# Whale_Lamp-jlc-v2.net
KiCad netlist of a schematic drawn in EAGLE
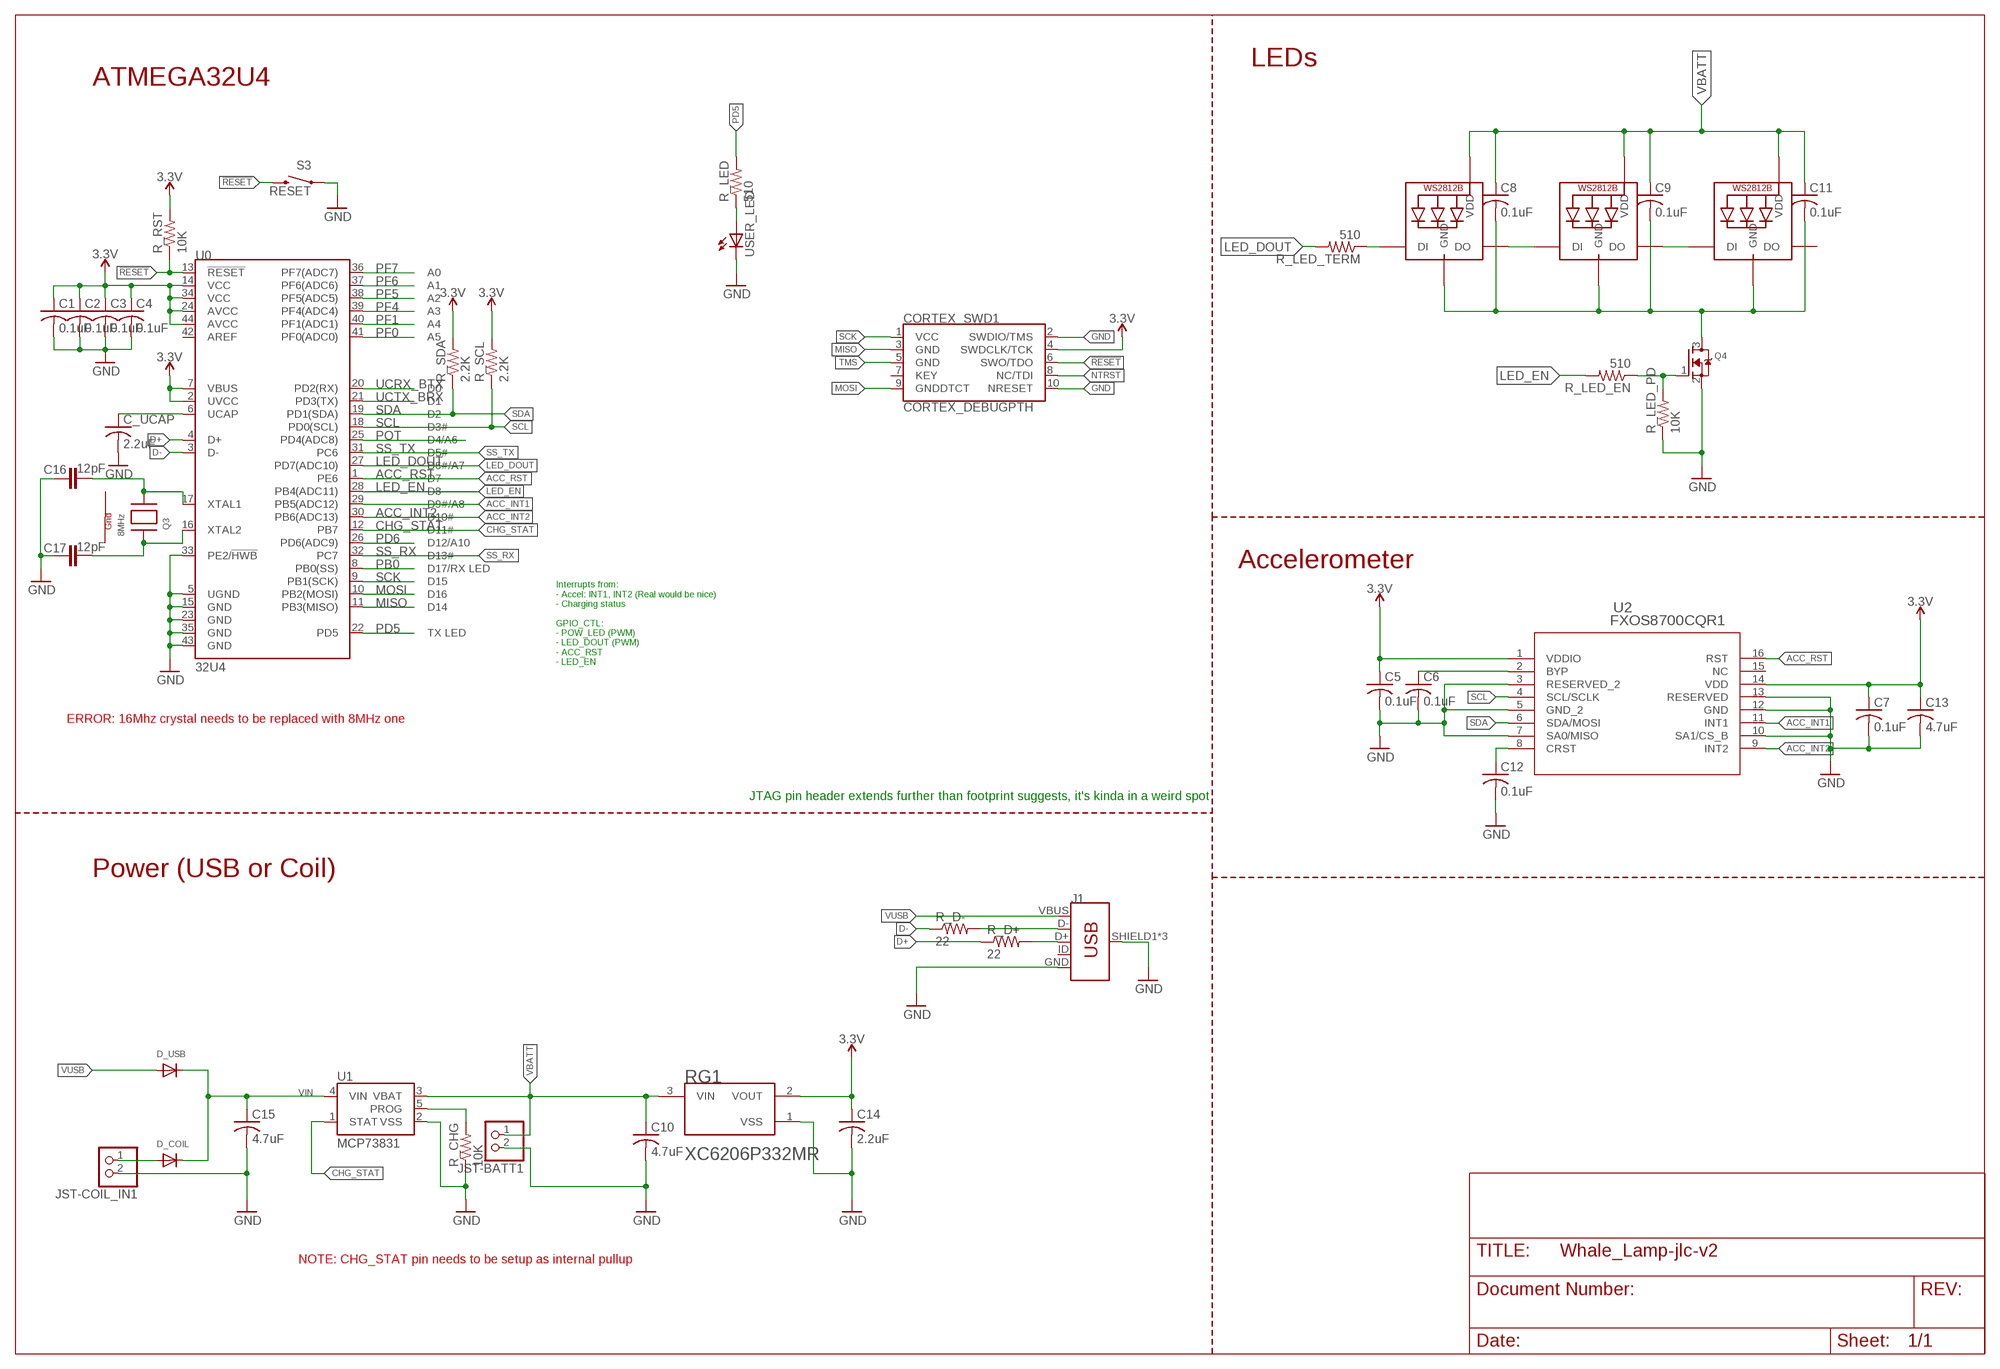
[diagram p0: schematic, sheet 1]

(export (version "E")
  (design (tool "Eeschema 10.0.6"))
  (components
    (comp (ref "C1")
      (value "0.1uF")
      (footprint "eagle-import:C0402")
      (libsource (lib "eagle-import") (part "C-USC0402"))
    )
    (comp (ref "C2")
      (value "0.1uF")
      (footprint "eagle-import:C0402")
      (libsource (lib "eagle-import") (part "C-USC0402"))
    )
    (comp (ref "C3")
      (value "0.1uF")
      (footprint "eagle-import:C0402")
      (libsource (lib "eagle-import") (part "C-USC0402"))
    )
    (comp (ref "C4")
      (value "0.1uF")
      (footprint "eagle-import:C0402")
      (libsource (lib "eagle-import") (part "C-USC0402"))
    )
    (comp (ref "C5")
      (value "0.1uF")
      (footprint "eagle-import:C0402")
      (libsource (lib "eagle-import") (part "C-USC0402"))
    )
    (comp (ref "C6")
      (value "0.1uF")
      (footprint "eagle-import:C0402")
      (libsource (lib "eagle-import") (part "C-USC0402"))
    )
    (comp (ref "C7")
      (value "0.1uF")
      (footprint "eagle-import:C0402")
      (libsource (lib "eagle-import") (part "C-USC0402"))
    )
    (comp (ref "C8")
      (value "0.1uF")
      (footprint "eagle-import:C0402")
      (libsource (lib "eagle-import") (part "C-USC0402"))
    )
    (comp (ref "C9")
      (value "0.1uF")
      (footprint "eagle-import:C0402")
      (libsource (lib "eagle-import") (part "C-USC0402"))
    )
    (comp (ref "C10")
      (value "4.7uF")
      (footprint "eagle-import:C0603")
      (libsource (lib "eagle-import") (part "C-USC0603"))
    )
    (comp (ref "C11")
      (value "0.1uF")
      (footprint "eagle-import:C0402")
      (libsource (lib "eagle-import") (part "C-USC0402"))
    )
    (comp (ref "C12")
      (value "0.1uF")
      (footprint "eagle-import:C0402")
      (libsource (lib "eagle-import") (part "C-USC0402"))
    )
    (comp (ref "C13")
      (value "4.7uF")
      (footprint "eagle-import:C0603")
      (libsource (lib "eagle-import") (part "C-USC0603"))
    )
    (comp (ref "C14")
      (value "2.2uF")
      (footprint "eagle-import:C0603")
      (libsource (lib "eagle-import") (part "C-USC0603"))
    )
    (comp (ref "C15")
      (value "4.7uF")
      (footprint "eagle-import:C0603")
      (libsource (lib "eagle-import") (part "C-USC0603"))
    )
    (comp (ref "C16")
      (value "12pF")
      (footprint "eagle-import:0402-CAP")
      (libsource (lib "eagle-import") (part "CAP0402-CAP"))
    )
    (comp (ref "C17")
      (value "12pF")
      (footprint "eagle-import:0402-CAP")
      (libsource (lib "eagle-import") (part "CAP0402-CAP"))
    )
    (comp (ref "CORTEX_SWD1")
      (value "CORTEX_DEBUGPTH")
      (footprint "eagle-import:2X5-PTH-1.27MM")
      (libsource (lib "eagle-import") (part "CORTEX_DEBUGPTH"))
    )
    (comp (ref "C_UCAP")
      (value "2.2uF")
      (footprint "eagle-import:C0603")
      (libsource (lib "eagle-import") (part "C-USC0603"))
    )
    (comp (ref "D_COIL")
      (value "DIODESOD-123")
      (footprint "eagle-import:SOD-123")
      (libsource (lib "eagle-import") (part "DIODESOD-123"))
    )
    (comp (ref "D_USB")
      (value "DIODESOD-123")
      (footprint "eagle-import:SOD-123")
      (libsource (lib "eagle-import") (part "DIODESOD-123"))
    )
    (comp (ref "J1")
      (value "USB_MICRO-B_FEMALE-SMT")
      (footprint "eagle-import:USB-B-MICRO-SMD")
      (libsource (lib "eagle-import") (part "USB_MICRO-B_FEMALE-SMT"))
    )
    (comp (ref "JST-BATT1")
      (value "JST_2PIN-THM-RA")
      (footprint "eagle-import:JST-PH-2-THM-RA")
      (libsource (lib "eagle-import") (part "JST_2PIN-THM-RA"))
    )
    (comp (ref "JST-COIL_IN1")
      (value "JST_2PIN-THM-RA")
      (footprint "eagle-import:JST-PH-2-THM-RA")
      (libsource (lib "eagle-import") (part "JST_2PIN-THM-RA"))
    )
    (comp (ref "LED1")
      (value "WS2812B3535")
      (footprint "eagle-import:LED3535")
      (libsource (lib "eagle-import") (part "WS2812B3535"))
    )
    (comp (ref "LED2")
      (value "WS2812B3535")
      (footprint "eagle-import:LED3535")
      (libsource (lib "eagle-import") (part "WS2812B3535"))
    )
    (comp (ref "LED3")
      (value "WS2812B3535")
      (footprint "eagle-import:LED3535")
      (libsource (lib "eagle-import") (part "WS2812B3535"))
    )
    (comp (ref "Q3")
      (value "8MHz")
      (footprint "eagle-import:NX3225")
      (libsource (lib "eagle-import") (part "XTAL-4-3225"))
    )
    (comp (ref "Q4")
      (value "MOSFET-NREFLOW")
      (footprint "eagle-import:SOT23")
      (libsource (lib "eagle-import") (part "MOSFET-NREFLOW"))
    )
    (comp (ref "RG1")
      (value "TOREX_XC6206P332MRTOREX_XC6206P332MR_0_0")
      (footprint "eagle-import:TOREX_XC6206P332MR_0")
      (fields
        (field (name "MF") "Torex")
        (field (name "MOUSER_PART_NUMBER") "865-XC6206P332MR-G")
        (field (name "MPN") "XC6206P332MR")
      )
      (libsource (lib "eagle-import") (part "TOREX_XC6206P332MRTOREX_XC6206P332MR_0_0"))
    )
    (comp (ref "R_CHG")
      (value "10K")
      (footprint "eagle-import:R0402")
      (libsource (lib "eagle-import") (part "R-US_R0402"))
    )
    (comp (ref "R_D+")
      (value "22")
      (footprint "eagle-import:R0402")
      (libsource (lib "eagle-import") (part "R-US_R0402"))
    )
    (comp (ref "R_D-")
      (value "22")
      (footprint "eagle-import:R0402")
      (libsource (lib "eagle-import") (part "R-US_R0402"))
    )
    (comp (ref "R_LED")
      (value "510")
      (footprint "eagle-import:R0402")
      (libsource (lib "eagle-import") (part "R-US_R0402"))
    )
    (comp (ref "R_LED_EN")
      (value "510")
      (footprint "eagle-import:R0402")
      (libsource (lib "eagle-import") (part "R-US_R0402"))
    )
    (comp (ref "R_LED_PD")
      (value "10K")
      (footprint "eagle-import:R0402")
      (libsource (lib "eagle-import") (part "R-US_R0402"))
    )
    (comp (ref "R_LED_TERM")
      (value "510")
      (footprint "eagle-import:R0402")
      (libsource (lib "eagle-import") (part "R-US_R0402"))
    )
    (comp (ref "R_RST")
      (value "10K")
      (footprint "eagle-import:R0402")
      (libsource (lib "eagle-import") (part "R-US_R0402"))
    )
    (comp (ref "R_SCL")
      (value "2.2K")
      (footprint "eagle-import:R0402")
      (libsource (lib "eagle-import") (part "R-US_R0402"))
    )
    (comp (ref "R_SDA")
      (value "2.2K")
      (footprint "eagle-import:R0402")
      (libsource (lib "eagle-import") (part "R-US_R0402"))
    )
    (comp (ref "S3")
      (value "RESET")
      (footprint "eagle-import:TACTILE_SWITCH_SMD_4.6X2.8MM")
      (libsource (lib "eagle-import") (part "SWITCH-MOMENTARY-2SMD-4.6X2.8MM"))
    )
    (comp (ref "U0")
      (value "32U4")
      (footprint "eagle-import:QFN-44")
      (libsource (lib "eagle-import") (part "ATMEGA32U4QFN"))
    )
    (comp (ref "U1")
      (value "MCP73831")
      (footprint "eagle-import:SOT23-5")
      (libsource (lib "eagle-import") (part "MCP73831"))
    )
    (comp (ref "U2")
      (value "FXOS8700CQR1")
      (footprint "eagle-import:QFN16_3X3_NXP")
      (fields (field (name "COPYRIGHT") "Copyright (C) 2018 Accelerated Designs. All rights reserved"))
      (libsource (lib "eagle-import") (part "FXOS8700CQR1"))
    )
    (comp (ref "USER_LED")
      (value "LEDCHIPLED_0603")
      (footprint "eagle-import:CHIPLED_0603")
      (libsource (lib "eagle-import") (part "LEDCHIPLED_0603"))
    )
  )
  (nets
    (net (code "1") (name "/G1") (class "Default")
      (node (ref "Q3") (pin "4") (pinfunction "G1_4") (pintype "power_in"))
    )
    (net (code "2") (name "/G2") (class "Default")
      (node (ref "Q3") (pin "2") (pinfunction "G2_2") (pintype "power_in"))
    )
    (net (code "3") (name "/PB0") (class "Default")
      (node (ref "U0") (pin "8") (pinfunction "PB0(SS)_8") (pintype "bidirectional"))
    )
    (net (code "4") (name "/PD6") (class "Default")
      (node (ref "U0") (pin "26") (pinfunction "PD6(ADC9)_26") (pintype "bidirectional"))
    )
    (net (code "5") (name "/PF0") (class "Default")
      (node (ref "U0") (pin "41") (pinfunction "PF0(ADC0)_41") (pintype "bidirectional"))
    )
    (net (code "6") (name "/PF1") (class "Default")
      (node (ref "U0") (pin "40") (pinfunction "PF1(ADC1)_40") (pintype "bidirectional"))
    )
    (net (code "7") (name "/PF4") (class "Default")
      (node (ref "U0") (pin "39") (pinfunction "PF4(ADC4)_39") (pintype "bidirectional"))
    )
    (net (code "8") (name "/PF5") (class "Default")
      (node (ref "U0") (pin "38") (pinfunction "PF5(ADC5)_38") (pintype "bidirectional"))
    )
    (net (code "9") (name "/PF6") (class "Default")
      (node (ref "U0") (pin "37") (pinfunction "PF6(ADC6)_37") (pintype "bidirectional"))
    )
    (net (code "10") (name "/PF7") (class "Default")
      (node (ref "U0") (pin "36") (pinfunction "PF7(ADC7)_36") (pintype "bidirectional"))
    )
    (net (code "11") (name "/POT") (class "Default")
      (node (ref "U0") (pin "25") (pinfunction "PD4(ADC8)_25") (pintype "bidirectional"))
    )
    (net (code "12") (name "/UCRX_BTX") (class "Default")
      (node (ref "U0") (pin "20") (pinfunction "PD2(RX)_20") (pintype "bidirectional"))
    )
    (net (code "13") (name "/UCTX_BRX") (class "Default")
      (node (ref "U0") (pin "21") (pinfunction "PD3(TX)_21") (pintype "bidirectional"))
    )
    (net (code "14") (name "/VIN") (class "Default")
      (node (ref "C15") (pin "1") (pinfunction "1_1") (pintype "passive"))
      (node (ref "D_COIL") (pin "C") (pinfunction "C_C") (pintype "passive"))
      (node (ref "D_USB") (pin "C") (pinfunction "C_C") (pintype "passive"))
      (node (ref "U1") (pin "4") (pinfunction "VIN_4") (pintype "power_in"))
    )
    (net (code "15") (name "/~{RESET}") (class "Default")
      (node (ref "CORTEX_SWD1") (pin "6") (pinfunction "SWO/TDO_6") (pintype "bidirectional"))
      (node (ref "R_RST") (pin "1") (pinfunction "1_1") (pintype "passive"))
      (node (ref "S3") (pin "3") (pinfunction "2_3") (pintype "passive"))
      (node (ref "S3") (pin "4") (pinfunction "2_4") (pintype "passive"))
      (node (ref "U0") (pin "13") (pinfunction "~{RESET}_13") (pintype "bidirectional"))
    )
    (net (code "16") (name "3.3V") (class "Default")
      (node (ref "C1") (pin "1") (pinfunction "1_1") (pintype "passive"))
      (node (ref "C13") (pin "1") (pinfunction "1_1") (pintype "passive"))
      (node (ref "C14") (pin "1") (pinfunction "1_1") (pintype "passive"))
      (node (ref "C2") (pin "1") (pinfunction "1_1") (pintype "passive"))
      (node (ref "C3") (pin "1") (pinfunction "1_1") (pintype "passive"))
      (node (ref "C4") (pin "1") (pinfunction "1_1") (pintype "passive"))
      (node (ref "C5") (pin "1") (pinfunction "1_1") (pintype "passive"))
      (node (ref "C7") (pin "1") (pinfunction "1_1") (pintype "passive"))
      (node (ref "CORTEX_SWD1") (pin "4") (pinfunction "SWDCLK/TCK_4") (pintype "bidirectional"))
      (node (ref "RG1") (pin "2") (pinfunction "VOUT_2") (pintype "bidirectional"))
      (node (ref "R_RST") (pin "2") (pinfunction "2_2") (pintype "passive"))
      (node (ref "R_SCL") (pin "2") (pinfunction "2_2") (pintype "passive"))
      (node (ref "R_SDA") (pin "2") (pinfunction "2_2") (pintype "passive"))
      (node (ref "U0") (pin "14") (pinfunction "VCC_14") (pintype "bidirectional"))
      (node (ref "U0") (pin "2") (pinfunction "UVCC_2") (pintype "bidirectional"))
      (node (ref "U0") (pin "24") (pinfunction "AVCC_24") (pintype "bidirectional"))
      (node (ref "U0") (pin "34") (pinfunction "VCC_34") (pintype "bidirectional"))
      (node (ref "U0") (pin "44") (pinfunction "AVCC_44") (pintype "bidirectional"))
      (node (ref "U0") (pin "7") (pinfunction "VBUS_7") (pintype "bidirectional"))
      (node (ref "U2") (pin "1") (pinfunction "VDDIO_1") (pintype "power_in"))
      (node (ref "U2") (pin "14") (pinfunction "VDD_14") (pintype "power_in"))
    )
    (net (code "17") (name "ACC_INT1") (class "Default")
      (node (ref "U0") (pin "29") (pinfunction "PB5(ADC12)_29") (pintype "bidirectional"))
      (node (ref "U2") (pin "11") (pinfunction "INT1_11") (pintype "bidirectional"))
    )
    (net (code "18") (name "ACC_INT2") (class "Default")
      (node (ref "U0") (pin "30") (pinfunction "PB6(ADC13)_30") (pintype "bidirectional"))
      (node (ref "U2") (pin "9") (pinfunction "INT2_9") (pintype "bidirectional"))
    )
    (net (code "19") (name "ACC_RST") (class "Default")
      (node (ref "U0") (pin "1") (pinfunction "PE6_1") (pintype "bidirectional"))
      (node (ref "U2") (pin "16") (pinfunction "RST_16") (pintype "input"))
    )
    (net (code "20") (name "CHG_STAT") (class "Default")
      (node (ref "U0") (pin "12") (pinfunction "PB7_12") (pintype "bidirectional"))
      (node (ref "U1") (pin "1") (pinfunction "STAT_1") (pintype "output"))
    )
    (net (code "21") (name "D+") (class "Default")
      (node (ref "R_D+") (pin "1") (pinfunction "1_1") (pintype "passive"))
      (node (ref "U0") (pin "4") (pinfunction "D+_4") (pintype "bidirectional"))
    )
    (net (code "22") (name "D-") (class "Default")
      (node (ref "R_D-") (pin "1") (pinfunction "1_1") (pintype "passive"))
      (node (ref "U0") (pin "3") (pinfunction "D-_3") (pintype "bidirectional"))
    )
    (net (code "23") (name "GND") (class "Default")
      (node (ref "C1") (pin "2") (pinfunction "2_2") (pintype "passive"))
      (node (ref "C10") (pin "2") (pinfunction "2_2") (pintype "passive"))
      (node (ref "C12") (pin "2") (pinfunction "2_2") (pintype "passive"))
      (node (ref "C13") (pin "2") (pinfunction "2_2") (pintype "passive"))
      (node (ref "C14") (pin "2") (pinfunction "2_2") (pintype "passive"))
      (node (ref "C15") (pin "2") (pinfunction "2_2") (pintype "passive"))
      (node (ref "C16") (pin "1") (pinfunction "1_1") (pintype "passive"))
      (node (ref "C17") (pin "1") (pinfunction "1_1") (pintype "passive"))
      (node (ref "C2") (pin "2") (pinfunction "2_2") (pintype "passive"))
      (node (ref "C3") (pin "2") (pinfunction "2_2") (pintype "passive"))
      (node (ref "C4") (pin "2") (pinfunction "2_2") (pintype "passive"))
      (node (ref "C5") (pin "2") (pinfunction "2_2") (pintype "passive"))
      (node (ref "C6") (pin "2") (pinfunction "2_2") (pintype "passive"))
      (node (ref "C7") (pin "2") (pinfunction "2_2") (pintype "passive"))
      (node (ref "CORTEX_SWD1") (pin "10") (pinfunction "NRESET_10") (pintype "bidirectional"))
      (node (ref "CORTEX_SWD1") (pin "2") (pinfunction "SWDIO/TMS_2") (pintype "bidirectional"))
      (node (ref "C_UCAP") (pin "2") (pinfunction "2_2") (pintype "passive"))
      (node (ref "J1") (pin "GND") (pinfunction "GND_GND") (pintype "power_in"))
      (node (ref "J1") (pin "SHIELD1") (pinfunction "SHIELD_SHIELD1") (pintype "bidirectional"))
      (node (ref "J1") (pin "SHIELD2") (pinfunction "SHIELD_SHIELD2") (pintype "bidirectional"))
      (node (ref "J1") (pin "SHIELD3") (pinfunction "SHIELD_SHIELD3") (pintype "bidirectional"))
      (node (ref "JST-BATT1") (pin "2") (pinfunction "1_2") (pintype "passive"))
      (node (ref "JST-COIL_IN1") (pin "2") (pinfunction "1_2") (pintype "passive"))
      (node (ref "Q4") (pin "2") (pinfunction "S_2") (pintype "bidirectional"))
      (node (ref "RG1") (pin "1") (pinfunction "VSS_1") (pintype "bidirectional"))
      (node (ref "R_CHG") (pin "1") (pinfunction "1_1") (pintype "passive"))
      (node (ref "R_LED_PD") (pin "1") (pinfunction "1_1") (pintype "passive"))
      (node (ref "S3") (pin "1") (pinfunction "1_1") (pintype "passive"))
      (node (ref "S3") (pin "2") (pinfunction "1_2") (pintype "passive"))
      (node (ref "U0") (pin "15") (pinfunction "GND_15") (pintype "bidirectional"))
      (node (ref "U0") (pin "23") (pinfunction "GND_23") (pintype "bidirectional"))
      (node (ref "U0") (pin "33") (pinfunction "PE2/~{HWB}_33") (pintype "bidirectional"))
      (node (ref "U0") (pin "35") (pinfunction "GND_35") (pintype "bidirectional"))
      (node (ref "U0") (pin "43") (pinfunction "GND_43") (pintype "bidirectional"))
      (node (ref "U0") (pin "5") (pinfunction "UGND_5") (pintype "bidirectional"))
      (node (ref "U1") (pin "2") (pinfunction "VSS_2") (pintype "power_in"))
      (node (ref "U2") (pin "10") (pinfunction "SA1/CS_B_10") (pintype "bidirectional"))
      (node (ref "U2") (pin "12") (pinfunction "GND_12") (pintype "power_in"))
      (node (ref "U2") (pin "13") (pinfunction "RESERVED_13") (pintype "passive"))
      (node (ref "U2") (pin "3") (pinfunction "RESERVED_2_3") (pintype "passive"))
      (node (ref "U2") (pin "5") (pinfunction "GND_2_5") (pintype "power_in"))
      (node (ref "U2") (pin "7") (pinfunction "SA0/MISO_7") (pintype "bidirectional"))
      (node (ref "USER_LED") (pin "C") (pinfunction "C_C") (pintype "passive"))
    )
    (net (code "24") (name "LED_DOUT") (class "Default")
      (node (ref "R_LED_TERM") (pin "2") (pinfunction "2_2") (pintype "passive"))
      (node (ref "U0") (pin "27") (pinfunction "PD7(ADC10)_27") (pintype "bidirectional"))
    )
    (net (code "25") (name "LED_EN") (class "Default")
      (node (ref "R_LED_EN") (pin "2") (pinfunction "2_2") (pintype "passive"))
      (node (ref "U0") (pin "28") (pinfunction "PB4(ADC11)_28") (pintype "bidirectional"))
    )
    (net (code "26") (name "MISO") (class "Default")
      (node (ref "CORTEX_SWD1") (pin "3") (pinfunction "GND_3") (pintype "bidirectional"))
      (node (ref "U0") (pin "11") (pinfunction "PB3(MISO)_11") (pintype "bidirectional"))
    )
    (net (code "27") (name "MOSI") (class "Default")
      (node (ref "CORTEX_SWD1") (pin "9") (pinfunction "GNDDTCT_9") (pintype "bidirectional"))
      (node (ref "U0") (pin "10") (pinfunction "PB2(MOSI)_10") (pintype "bidirectional"))
    )
    (net (code "28") (name "NTRST") (class "Default")
      (node (ref "CORTEX_SWD1") (pin "8") (pinfunction "NC/TDI_8") (pintype "bidirectional"))
    )
    (net (code "29") (name "Net-(J1-PadD+)") (class "Default")
      (node (ref "J1") (pin "D+") (pinfunction "D+_D+") (pintype "bidirectional"))
      (node (ref "R_D+") (pin "2") (pinfunction "2_2") (pintype "passive"))
    )
    (net (code "30") (name "Net-(J1-PadD-)") (class "Default")
      (node (ref "J1") (pin "D-") (pinfunction "D-_D-") (pintype "bidirectional"))
      (node (ref "R_D-") (pin "2") (pinfunction "2_2") (pintype "passive"))
    )
    (net (code "31") (name "Net-(JST-COIL_IN1-2)") (class "Default")
      (node (ref "D_COIL") (pin "A") (pinfunction "A_A") (pintype "passive"))
      (node (ref "JST-COIL_IN1") (pin "1") (pinfunction "2_1") (pintype "passive"))
    )
    (net (code "32") (name "Net-(LED1-DI)") (class "Default")
      (node (ref "LED1") (pin "1") (pinfunction "DI_1") (pintype "input"))
      (node (ref "R_LED_TERM") (pin "1") (pinfunction "1_1") (pintype "passive"))
    )
    (net (code "33") (name "Net-(LED1-DO)") (class "Default")
      (node (ref "LED1") (pin "3") (pinfunction "DO_3") (pintype "output"))
      (node (ref "LED2") (pin "1") (pinfunction "DI_1") (pintype "input"))
    )
    (net (code "34") (name "Net-(LED1-GND)") (class "Default")
      (node (ref "C11") (pin "2") (pinfunction "2_2") (pintype "passive"))
      (node (ref "C8") (pin "2") (pinfunction "2_2") (pintype "passive"))
      (node (ref "C9") (pin "2") (pinfunction "2_2") (pintype "passive"))
      (node (ref "LED1") (pin "4") (pinfunction "GND_4") (pintype "power_in"))
      (node (ref "LED2") (pin "4") (pinfunction "GND_4") (pintype "power_in"))
      (node (ref "LED3") (pin "4") (pinfunction "GND_4") (pintype "power_in"))
      (node (ref "Q4") (pin "3") (pinfunction "D_3") (pintype "bidirectional"))
    )
    (net (code "35") (name "Net-(LED2-DO)") (class "Default")
      (node (ref "LED2") (pin "3") (pinfunction "DO_3") (pintype "output"))
      (node (ref "LED3") (pin "1") (pinfunction "DI_1") (pintype "input"))
    )
    (net (code "36") (name "Net-(Q3-X1)") (class "Default")
      (node (ref "C17") (pin "2") (pinfunction "2_2") (pintype "passive"))
      (node (ref "Q3") (pin "1") (pinfunction "X1_1") (pintype "bidirectional"))
      (node (ref "U0") (pin "16") (pinfunction "XTAL2_16") (pintype "bidirectional"))
    )
    (net (code "37") (name "Net-(Q3-X2)") (class "Default")
      (node (ref "C16") (pin "2") (pinfunction "2_2") (pintype "passive"))
      (node (ref "Q3") (pin "3") (pinfunction "X2_3") (pintype "bidirectional"))
      (node (ref "U0") (pin "17") (pinfunction "XTAL1_17") (pintype "bidirectional"))
    )
    (net (code "38") (name "Net-(Q4-G)") (class "Default")
      (node (ref "Q4") (pin "1") (pinfunction "G_1") (pintype "bidirectional"))
      (node (ref "R_LED_EN") (pin "1") (pinfunction "1_1") (pintype "passive"))
      (node (ref "R_LED_PD") (pin "2") (pinfunction "2_2") (pintype "passive"))
    )
    (net (code "39") (name "Net-(R_LED-Pad1)") (class "Default")
      (node (ref "R_LED") (pin "1") (pinfunction "1_1") (pintype "passive"))
      (node (ref "USER_LED") (pin "A") (pinfunction "A_A") (pintype "passive"))
    )
    (net (code "40") (name "Net-(U0-UCAP)") (class "Default")
      (node (ref "C_UCAP") (pin "1") (pinfunction "1_1") (pintype "passive"))
      (node (ref "U0") (pin "6") (pinfunction "UCAP_6") (pintype "bidirectional"))
    )
    (net (code "41") (name "Net-(U1-PROG)") (class "Default")
      (node (ref "R_CHG") (pin "2") (pinfunction "2_2") (pintype "passive"))
      (node (ref "U1") (pin "5") (pinfunction "PROG_5") (pintype "input"))
    )
    (net (code "42") (name "Net-(U2-BYP)") (class "Default")
      (node (ref "C6") (pin "1") (pinfunction "1_1") (pintype "passive"))
      (node (ref "U2") (pin "2") (pinfunction "BYP_2") (pintype "output"))
    )
    (net (code "43") (name "Net-(U2-CRST)") (class "Default")
      (node (ref "C12") (pin "1") (pinfunction "1_1") (pintype "passive"))
      (node (ref "U2") (pin "8") (pinfunction "CRST_8") (pintype "bidirectional"))
    )
    (net (code "44") (name "PD5") (class "Default")
      (node (ref "R_LED") (pin "2") (pinfunction "2_2") (pintype "passive"))
      (node (ref "U0") (pin "22") (pinfunction "PD5_22") (pintype "bidirectional"))
    )
    (net (code "45") (name "SCK") (class "Default")
      (node (ref "CORTEX_SWD1") (pin "1") (pinfunction "VCC_1") (pintype "bidirectional"))
      (node (ref "U0") (pin "9") (pinfunction "PB1(SCK)_9") (pintype "bidirectional"))
    )
    (net (code "46") (name "SCL") (class "Default")
      (node (ref "R_SCL") (pin "1") (pinfunction "1_1") (pintype "passive"))
      (node (ref "U0") (pin "18") (pinfunction "PD0(SCL)_18") (pintype "bidirectional"))
      (node (ref "U2") (pin "4") (pinfunction "SCL/SCLK_4") (pintype "input"))
    )
    (net (code "47") (name "SDA") (class "Default")
      (node (ref "R_SDA") (pin "1") (pinfunction "1_1") (pintype "passive"))
      (node (ref "U0") (pin "19") (pinfunction "PD1(SDA)_19") (pintype "bidirectional"))
      (node (ref "U2") (pin "6") (pinfunction "SDA/MOSI_6") (pintype "bidirectional"))
    )
    (net (code "48") (name "SS_RX") (class "Default")
      (node (ref "U0") (pin "32") (pinfunction "PC7_32") (pintype "bidirectional"))
    )
    (net (code "49") (name "SS_TX") (class "Default")
      (node (ref "U0") (pin "31") (pinfunction "PC6_31") (pintype "bidirectional"))
    )
    (net (code "50") (name "TMS") (class "Default")
      (node (ref "CORTEX_SWD1") (pin "5") (pinfunction "GND_5") (pintype "bidirectional"))
    )
    (net (code "51") (name "VBATT") (class "Default")
      (node (ref "C10") (pin "1") (pinfunction "1_1") (pintype "passive"))
      (node (ref "C11") (pin "1") (pinfunction "1_1") (pintype "passive"))
      (node (ref "C8") (pin "1") (pinfunction "1_1") (pintype "passive"))
      (node (ref "C9") (pin "1") (pinfunction "1_1") (pintype "passive"))
      (node (ref "JST-BATT1") (pin "1") (pinfunction "2_1") (pintype "passive"))
      (node (ref "LED1") (pin "2") (pinfunction "VDD_2") (pintype "power_in"))
      (node (ref "LED2") (pin "2") (pinfunction "VDD_2") (pintype "power_in"))
      (node (ref "LED3") (pin "2") (pinfunction "VDD_2") (pintype "power_in"))
      (node (ref "RG1") (pin "3") (pinfunction "VIN_3") (pintype "bidirectional"))
      (node (ref "U1") (pin "3") (pinfunction "VBAT_3") (pintype "power_in"))
    )
    (net (code "52") (name "VUSB") (class "Default")
      (node (ref "D_USB") (pin "A") (pinfunction "A_A") (pintype "passive"))
      (node (ref "J1") (pin "VBUS") (pinfunction "VBUS_VBUS") (pintype "power_in"))
    )
    (net (code "53") (name "unconnected-(CORTEX_SWD1-KEY-Pad7)") (class "Default")
      (node (ref "CORTEX_SWD1") (pin "7") (pinfunction "KEY_7") (pintype "bidirectional"))
    )
    (net (code "54") (name "unconnected-(J1-PadID)") (class "Default")
      (node (ref "J1") (pin "ID") (pinfunction "ID_ID") (pintype "bidirectional"))
    )
    (net (code "55") (name "unconnected-(LED3-DO-Pad3)") (class "Default")
      (node (ref "LED3") (pin "3") (pinfunction "DO_3") (pintype "output"))
    )
    (net (code "56") (name "unconnected-(U0-AREF-Pad42)") (class "Default")
      (node (ref "U0") (pin "42") (pinfunction "AREF_42") (pintype "bidirectional"))
    )
    (net (code "57") (name "unconnected-(U2-NC-Pad15)") (class "Default")
      (node (ref "U2") (pin "15") (pinfunction "NC_15") (pintype "no_connect"))
    )
  )
)
